# imsensor-v01.net
KiCad netlist of a schematic drawn in EAGLE
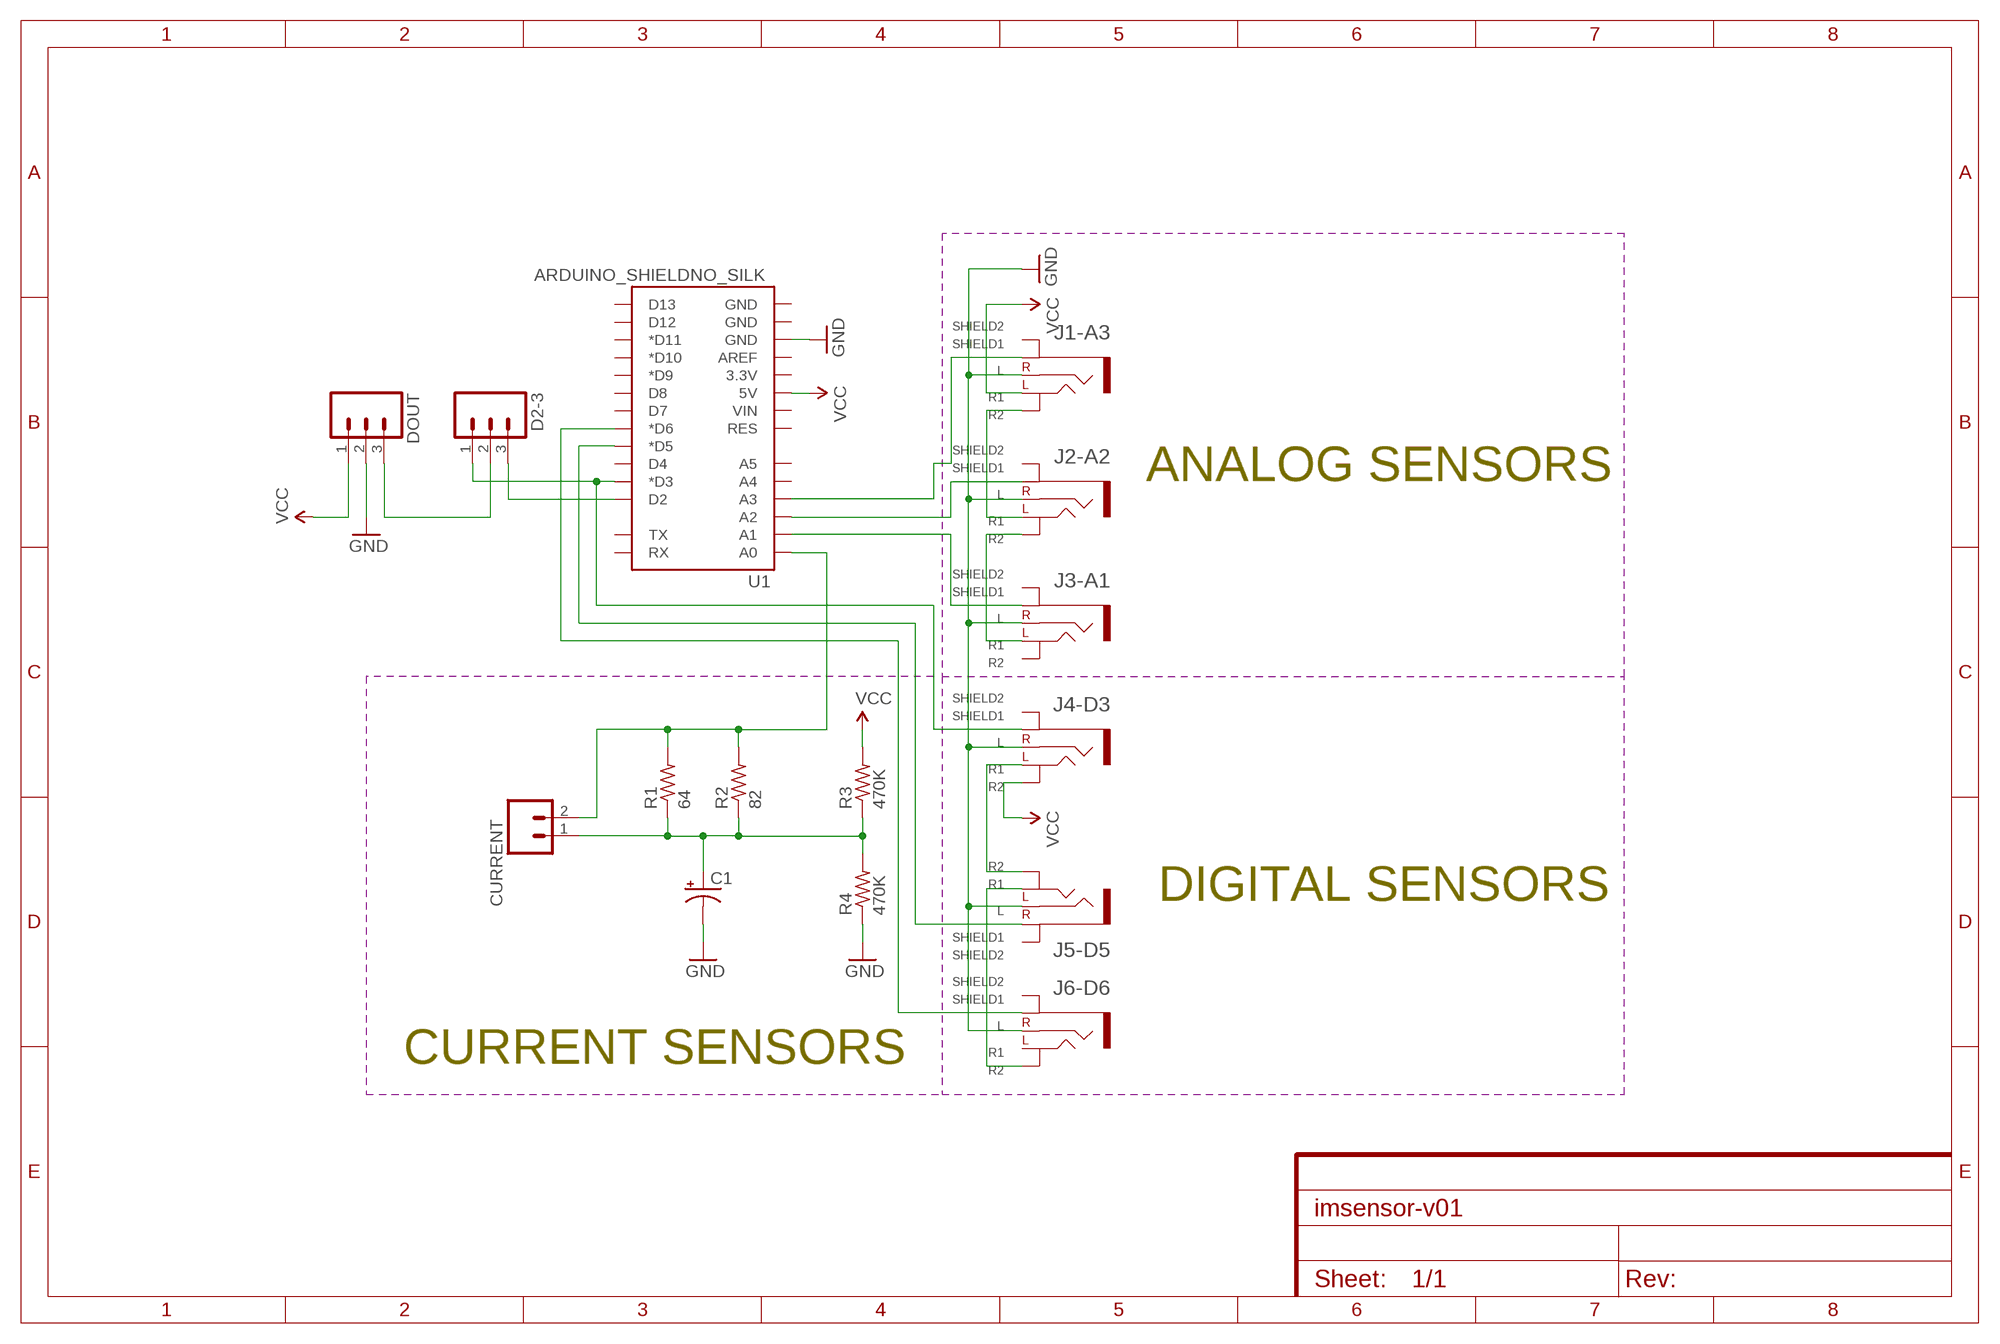
[diagram p0: schematic, sheet 1]

(export (version "E")
  (design (tool "Eeschema 10.0.6"))
  (components
    (comp (ref "C1")
      (value "10UF-25V-20%(PTH)")
      (footprint "eagle-import:CPOL-RADIAL-10UF-25V")
      (libsource (lib "eagle-import") (part "10UF-25V-20%(PTH)"))
    )
    (comp (ref "CURRENT")
      (value "M02PTH")
      (footprint "eagle-import:1X02")
      (libsource (lib "eagle-import") (part "M02PTH"))
    )
    (comp (ref "D2-3")
      (value "M03PTH")
      (footprint "eagle-import:1X03")
      (libsource (lib "eagle-import") (part "M03PTH"))
    )
    (comp (ref "DOUT")
      (value "M03PTH")
      (footprint "eagle-import:1X03")
      (libsource (lib "eagle-import") (part "M03PTH"))
    )
    (comp (ref "J1-A3")
      (value "PJ-313-SPAD")
      (footprint "eagle-import:PJ-313-5PIN-SMALL")
      (libsource (lib "eagle-import") (part "PJ-313-SPAD"))
    )
    (comp (ref "J2-A2")
      (value "PJ-313-SPAD")
      (footprint "eagle-import:PJ-313-5PIN-SMALL")
      (libsource (lib "eagle-import") (part "PJ-313-SPAD"))
    )
    (comp (ref "J3-A1")
      (value "PJ-313-SPAD")
      (footprint "eagle-import:PJ-313-5PIN-SMALL")
      (libsource (lib "eagle-import") (part "PJ-313-SPAD"))
    )
    (comp (ref "J4-D3")
      (value "PJ-313-SPAD")
      (footprint "eagle-import:PJ-313-5PIN-SMALL")
      (libsource (lib "eagle-import") (part "PJ-313-SPAD"))
    )
    (comp (ref "J5-D5")
      (value "PJ-313-SPAD")
      (footprint "eagle-import:PJ-313-5PIN-SMALL")
      (libsource (lib "eagle-import") (part "PJ-313-SPAD"))
    )
    (comp (ref "J6-D6")
      (value "PJ-313-SPAD")
      (footprint "eagle-import:PJ-313-5PIN-SMALL")
      (libsource (lib "eagle-import") (part "PJ-313-SPAD"))
    )
    (comp (ref "R1")
      (value "64")
      (footprint "eagle-import:0207_10")
      (libsource (lib "eagle-import") (part "R-US_0207/10"))
    )
    (comp (ref "R2")
      (value "82")
      (footprint "eagle-import:0207_10")
      (libsource (lib "eagle-import") (part "R-US_0207/10"))
    )
    (comp (ref "R3")
      (value "470K")
      (footprint "eagle-import:0207_10")
      (libsource (lib "eagle-import") (part "R-US_0207/10"))
    )
    (comp (ref "R4")
      (value "470K")
      (footprint "eagle-import:0207_10")
      (libsource (lib "eagle-import") (part "R-US_0207/10"))
    )
    (comp (ref "U1")
      (value "ARDUINO_SHIELDNO_SILK")
      (footprint "eagle-import:DUEMILANOVE_VIAS")
      (libsource (lib "eagle-import") (part "ARDUINO_SHIELDNO_SILK"))
    )
  )
  (nets
    (net (code "1") (name "GND") (class "Default")
      (node (ref "C1") (pin "2") (pinfunction "-_2") (pintype "passive"))
      (node (ref "DOUT") (pin "2") (pinfunction "2_2") (pintype "passive"))
      (node (ref "J1-A3") (pin "2") (pinfunction "R_2") (pintype "bidirectional"))
      (node (ref "J2-A2") (pin "2") (pinfunction "R_2") (pintype "bidirectional"))
      (node (ref "J3-A1") (pin "2") (pinfunction "R_2") (pintype "bidirectional"))
      (node (ref "J4-D3") (pin "2") (pinfunction "R_2") (pintype "bidirectional"))
      (node (ref "J5-D5") (pin "2") (pinfunction "R_2") (pintype "bidirectional"))
      (node (ref "J6-D6") (pin "2") (pinfunction "R_2") (pintype "bidirectional"))
      (node (ref "R4") (pin "1") (pinfunction "1_1") (pintype "passive"))
      (node (ref "U1") (pin "GND@2") (pinfunction "GND_GND@2") (pintype "bidirectional"))
    )
    (net (code "2") (name "Net-(C1-+)") (class "Default")
      (node (ref "C1") (pin "1") (pinfunction "+_1") (pintype "passive"))
      (node (ref "CURRENT") (pin "1") (pinfunction "1_1") (pintype "passive"))
      (node (ref "R1") (pin "1") (pinfunction "1_1") (pintype "passive"))
      (node (ref "R2") (pin "1") (pinfunction "1_1") (pintype "passive"))
      (node (ref "R3") (pin "1") (pinfunction "1_1") (pintype "passive"))
      (node (ref "R4") (pin "2") (pinfunction "2_2") (pintype "passive"))
    )
    (net (code "3") (name "Net-(CURRENT-Pad2)") (class "Default")
      (node (ref "CURRENT") (pin "2") (pinfunction "2_2") (pintype "passive"))
      (node (ref "R1") (pin "2") (pinfunction "2_2") (pintype "passive"))
      (node (ref "R2") (pin "2") (pinfunction "2_2") (pintype "passive"))
      (node (ref "U1") (pin "A0") (pinfunction "A0_A0") (pintype "bidirectional"))
    )
    (net (code "4") (name "Net-(D2-3-Pad2)") (class "Default")
      (node (ref "D2-3") (pin "2") (pinfunction "2_2") (pintype "passive"))
      (node (ref "DOUT") (pin "3") (pinfunction "3_3") (pintype "passive"))
    )
    (net (code "5") (name "Net-(D2-3-Pad3)") (class "Default")
      (node (ref "D2-3") (pin "3") (pinfunction "3_3") (pintype "passive"))
      (node (ref "U1") (pin "D2") (pinfunction "D2_D2") (pintype "bidirectional"))
    )
    (net (code "6") (name "Net-(J1-A3-L2)") (class "Default")
      (node (ref "J1-A3") (pin "3.2") (pinfunction "L2_3.2") (pintype "bidirectional"))
      (node (ref "J2-A2") (pin "3.1") (pinfunction "L1_3.1") (pintype "bidirectional"))
    )
    (net (code "7") (name "Net-(J1-A3-SHIELD1)") (class "Default")
      (node (ref "J1-A3") (pin "1.1") (pinfunction "SHIELD1_1.1") (pintype "bidirectional"))
      (node (ref "U1") (pin "A3") (pinfunction "A3_A3") (pintype "bidirectional"))
    )
    (net (code "8") (name "Net-(J2-A2-L2)") (class "Default")
      (node (ref "J2-A2") (pin "3.2") (pinfunction "L2_3.2") (pintype "bidirectional"))
      (node (ref "J3-A1") (pin "3.1") (pinfunction "L1_3.1") (pintype "bidirectional"))
    )
    (net (code "9") (name "Net-(J2-A2-SHIELD1)") (class "Default")
      (node (ref "J2-A2") (pin "1.1") (pinfunction "SHIELD1_1.1") (pintype "bidirectional"))
      (node (ref "U1") (pin "A2") (pinfunction "A2_A2") (pintype "bidirectional"))
    )
    (net (code "10") (name "Net-(J3-A1-SHIELD1)") (class "Default")
      (node (ref "J3-A1") (pin "1.1") (pinfunction "SHIELD1_1.1") (pintype "bidirectional"))
      (node (ref "U1") (pin "A1") (pinfunction "A1_A1") (pintype "bidirectional"))
    )
    (net (code "11") (name "Net-(J4-D3-L1)") (class "Default")
      (node (ref "J4-D3") (pin "3.1") (pinfunction "L1_3.1") (pintype "bidirectional"))
      (node (ref "J5-D5") (pin "3.2") (pinfunction "L2_3.2") (pintype "bidirectional"))
    )
    (net (code "12") (name "Net-(J4-D3-SHIELD1)") (class "Default")
      (node (ref "D2-3") (pin "1") (pinfunction "1_1") (pintype "passive"))
      (node (ref "J4-D3") (pin "1.1") (pinfunction "SHIELD1_1.1") (pintype "bidirectional"))
      (node (ref "U1") (pin "D3") (pinfunction "*D3_D3") (pintype "bidirectional"))
    )
    (net (code "13") (name "Net-(J5-D5-L1)") (class "Default")
      (node (ref "J5-D5") (pin "3.1") (pinfunction "L1_3.1") (pintype "bidirectional"))
      (node (ref "J6-D6") (pin "3.2") (pinfunction "L2_3.2") (pintype "bidirectional"))
    )
    (net (code "14") (name "Net-(J5-D5-SHIELD1)") (class "Default")
      (node (ref "J5-D5") (pin "1.1") (pinfunction "SHIELD1_1.1") (pintype "bidirectional"))
      (node (ref "U1") (pin "D5") (pinfunction "*D5_D5") (pintype "bidirectional"))
    )
    (net (code "15") (name "Net-(J6-D6-SHIELD1)") (class "Default")
      (node (ref "J6-D6") (pin "1.1") (pinfunction "SHIELD1_1.1") (pintype "bidirectional"))
      (node (ref "U1") (pin "D6") (pinfunction "*D6_D6") (pintype "bidirectional"))
    )
    (net (code "16") (name "VCC") (class "Default")
      (node (ref "DOUT") (pin "1") (pinfunction "1_1") (pintype "passive"))
      (node (ref "J1-A3") (pin "3.1") (pinfunction "L1_3.1") (pintype "bidirectional"))
      (node (ref "J4-D3") (pin "3.2") (pinfunction "L2_3.2") (pintype "bidirectional"))
      (node (ref "R3") (pin "2") (pinfunction "2_2") (pintype "passive"))
      (node (ref "U1") (pin "5V") (pinfunction "5V_5V") (pintype "bidirectional"))
    )
    (net (code "17") (name "unconnected-(J1-A3-SHIELD2-Pad1.2)") (class "Default")
      (node (ref "J1-A3") (pin "1.2") (pinfunction "SHIELD2_1.2") (pintype "bidirectional"))
    )
    (net (code "18") (name "unconnected-(J2-A2-SHIELD2-Pad1.2)") (class "Default")
      (node (ref "J2-A2") (pin "1.2") (pinfunction "SHIELD2_1.2") (pintype "bidirectional"))
    )
    (net (code "19") (name "unconnected-(J3-A1-L2-Pad3.2)") (class "Default")
      (node (ref "J3-A1") (pin "3.2") (pinfunction "L2_3.2") (pintype "bidirectional"))
    )
    (net (code "20") (name "unconnected-(J3-A1-SHIELD2-Pad1.2)") (class "Default")
      (node (ref "J3-A1") (pin "1.2") (pinfunction "SHIELD2_1.2") (pintype "bidirectional"))
    )
    (net (code "21") (name "unconnected-(J4-D3-SHIELD2-Pad1.2)") (class "Default")
      (node (ref "J4-D3") (pin "1.2") (pinfunction "SHIELD2_1.2") (pintype "bidirectional"))
    )
    (net (code "22") (name "unconnected-(J5-D5-SHIELD2-Pad1.2)") (class "Default")
      (node (ref "J5-D5") (pin "1.2") (pinfunction "SHIELD2_1.2") (pintype "bidirectional"))
    )
    (net (code "23") (name "unconnected-(J6-D6-L1-Pad3.1)") (class "Default")
      (node (ref "J6-D6") (pin "3.1") (pinfunction "L1_3.1") (pintype "bidirectional"))
    )
    (net (code "24") (name "unconnected-(J6-D6-SHIELD2-Pad1.2)") (class "Default")
      (node (ref "J6-D6") (pin "1.2") (pinfunction "SHIELD2_1.2") (pintype "bidirectional"))
    )
    (net (code "25") (name "unconnected-(U1-*D9-PadD9)") (class "Default")
      (node (ref "U1") (pin "D9") (pinfunction "*D9_D9") (pintype "bidirectional"))
    )
    (net (code "26") (name "unconnected-(U1-*D10-PadD10)") (class "Default")
      (node (ref "U1") (pin "D10") (pinfunction "*D10_D10") (pintype "bidirectional"))
    )
    (net (code "27") (name "unconnected-(U1-*D11-PadD11)") (class "Default")
      (node (ref "U1") (pin "D11") (pinfunction "*D11_D11") (pintype "bidirectional"))
    )
    (net (code "28") (name "unconnected-(U1-GND-PadGND@0)") (class "Default")
      (node (ref "U1") (pin "GND@0") (pinfunction "GND_GND@0") (pintype "bidirectional"))
    )
    (net (code "29") (name "unconnected-(U1-GND-PadGND@1)") (class "Default")
      (node (ref "U1") (pin "GND@1") (pinfunction "GND_GND@1") (pintype "bidirectional"))
    )
    (net (code "30") (name "unconnected-(U1-Pad3.3V)") (class "Default")
      (node (ref "U1") (pin "3.3V") (pinfunction "3.3V_3.3V") (pintype "bidirectional"))
    )
    (net (code "31") (name "unconnected-(U1-PadA4)") (class "Default")
      (node (ref "U1") (pin "A4") (pinfunction "A4_A4") (pintype "bidirectional"))
    )
    (net (code "32") (name "unconnected-(U1-PadA5)") (class "Default")
      (node (ref "U1") (pin "A5") (pinfunction "A5_A5") (pintype "bidirectional"))
    )
    (net (code "33") (name "unconnected-(U1-PadAREF)") (class "Default")
      (node (ref "U1") (pin "AREF") (pinfunction "AREF_AREF") (pintype "bidirectional"))
    )
    (net (code "34") (name "unconnected-(U1-PadD4)") (class "Default")
      (node (ref "U1") (pin "D4") (pinfunction "D4_D4") (pintype "bidirectional"))
    )
    (net (code "35") (name "unconnected-(U1-PadD7)") (class "Default")
      (node (ref "U1") (pin "D7") (pinfunction "D7_D7") (pintype "bidirectional"))
    )
    (net (code "36") (name "unconnected-(U1-PadD8)") (class "Default")
      (node (ref "U1") (pin "D8") (pinfunction "D8_D8") (pintype "bidirectional"))
    )
    (net (code "37") (name "unconnected-(U1-PadD12)") (class "Default")
      (node (ref "U1") (pin "D12") (pinfunction "D12_D12") (pintype "bidirectional"))
    )
    (net (code "38") (name "unconnected-(U1-PadD13)") (class "Default")
      (node (ref "U1") (pin "D13") (pinfunction "D13_D13") (pintype "bidirectional"))
    )
    (net (code "39") (name "unconnected-(U1-PadRES)") (class "Default")
      (node (ref "U1") (pin "RES") (pinfunction "RES_RES") (pintype "bidirectional"))
    )
    (net (code "40") (name "unconnected-(U1-PadRX)") (class "Default")
      (node (ref "U1") (pin "RX") (pinfunction "RX_RX") (pintype "bidirectional"))
    )
    (net (code "41") (name "unconnected-(U1-PadTX)") (class "Default")
      (node (ref "U1") (pin "TX") (pinfunction "TX_TX") (pintype "bidirectional"))
    )
    (net (code "42") (name "unconnected-(U1-PadVIN)") (class "Default")
      (node (ref "U1") (pin "VIN") (pinfunction "VIN_VIN") (pintype "bidirectional"))
    )
  )
)
